# 1-Schematic_PCnA_FinalProject.net
KiCad netlist of a schematic drawn in EasyEDA
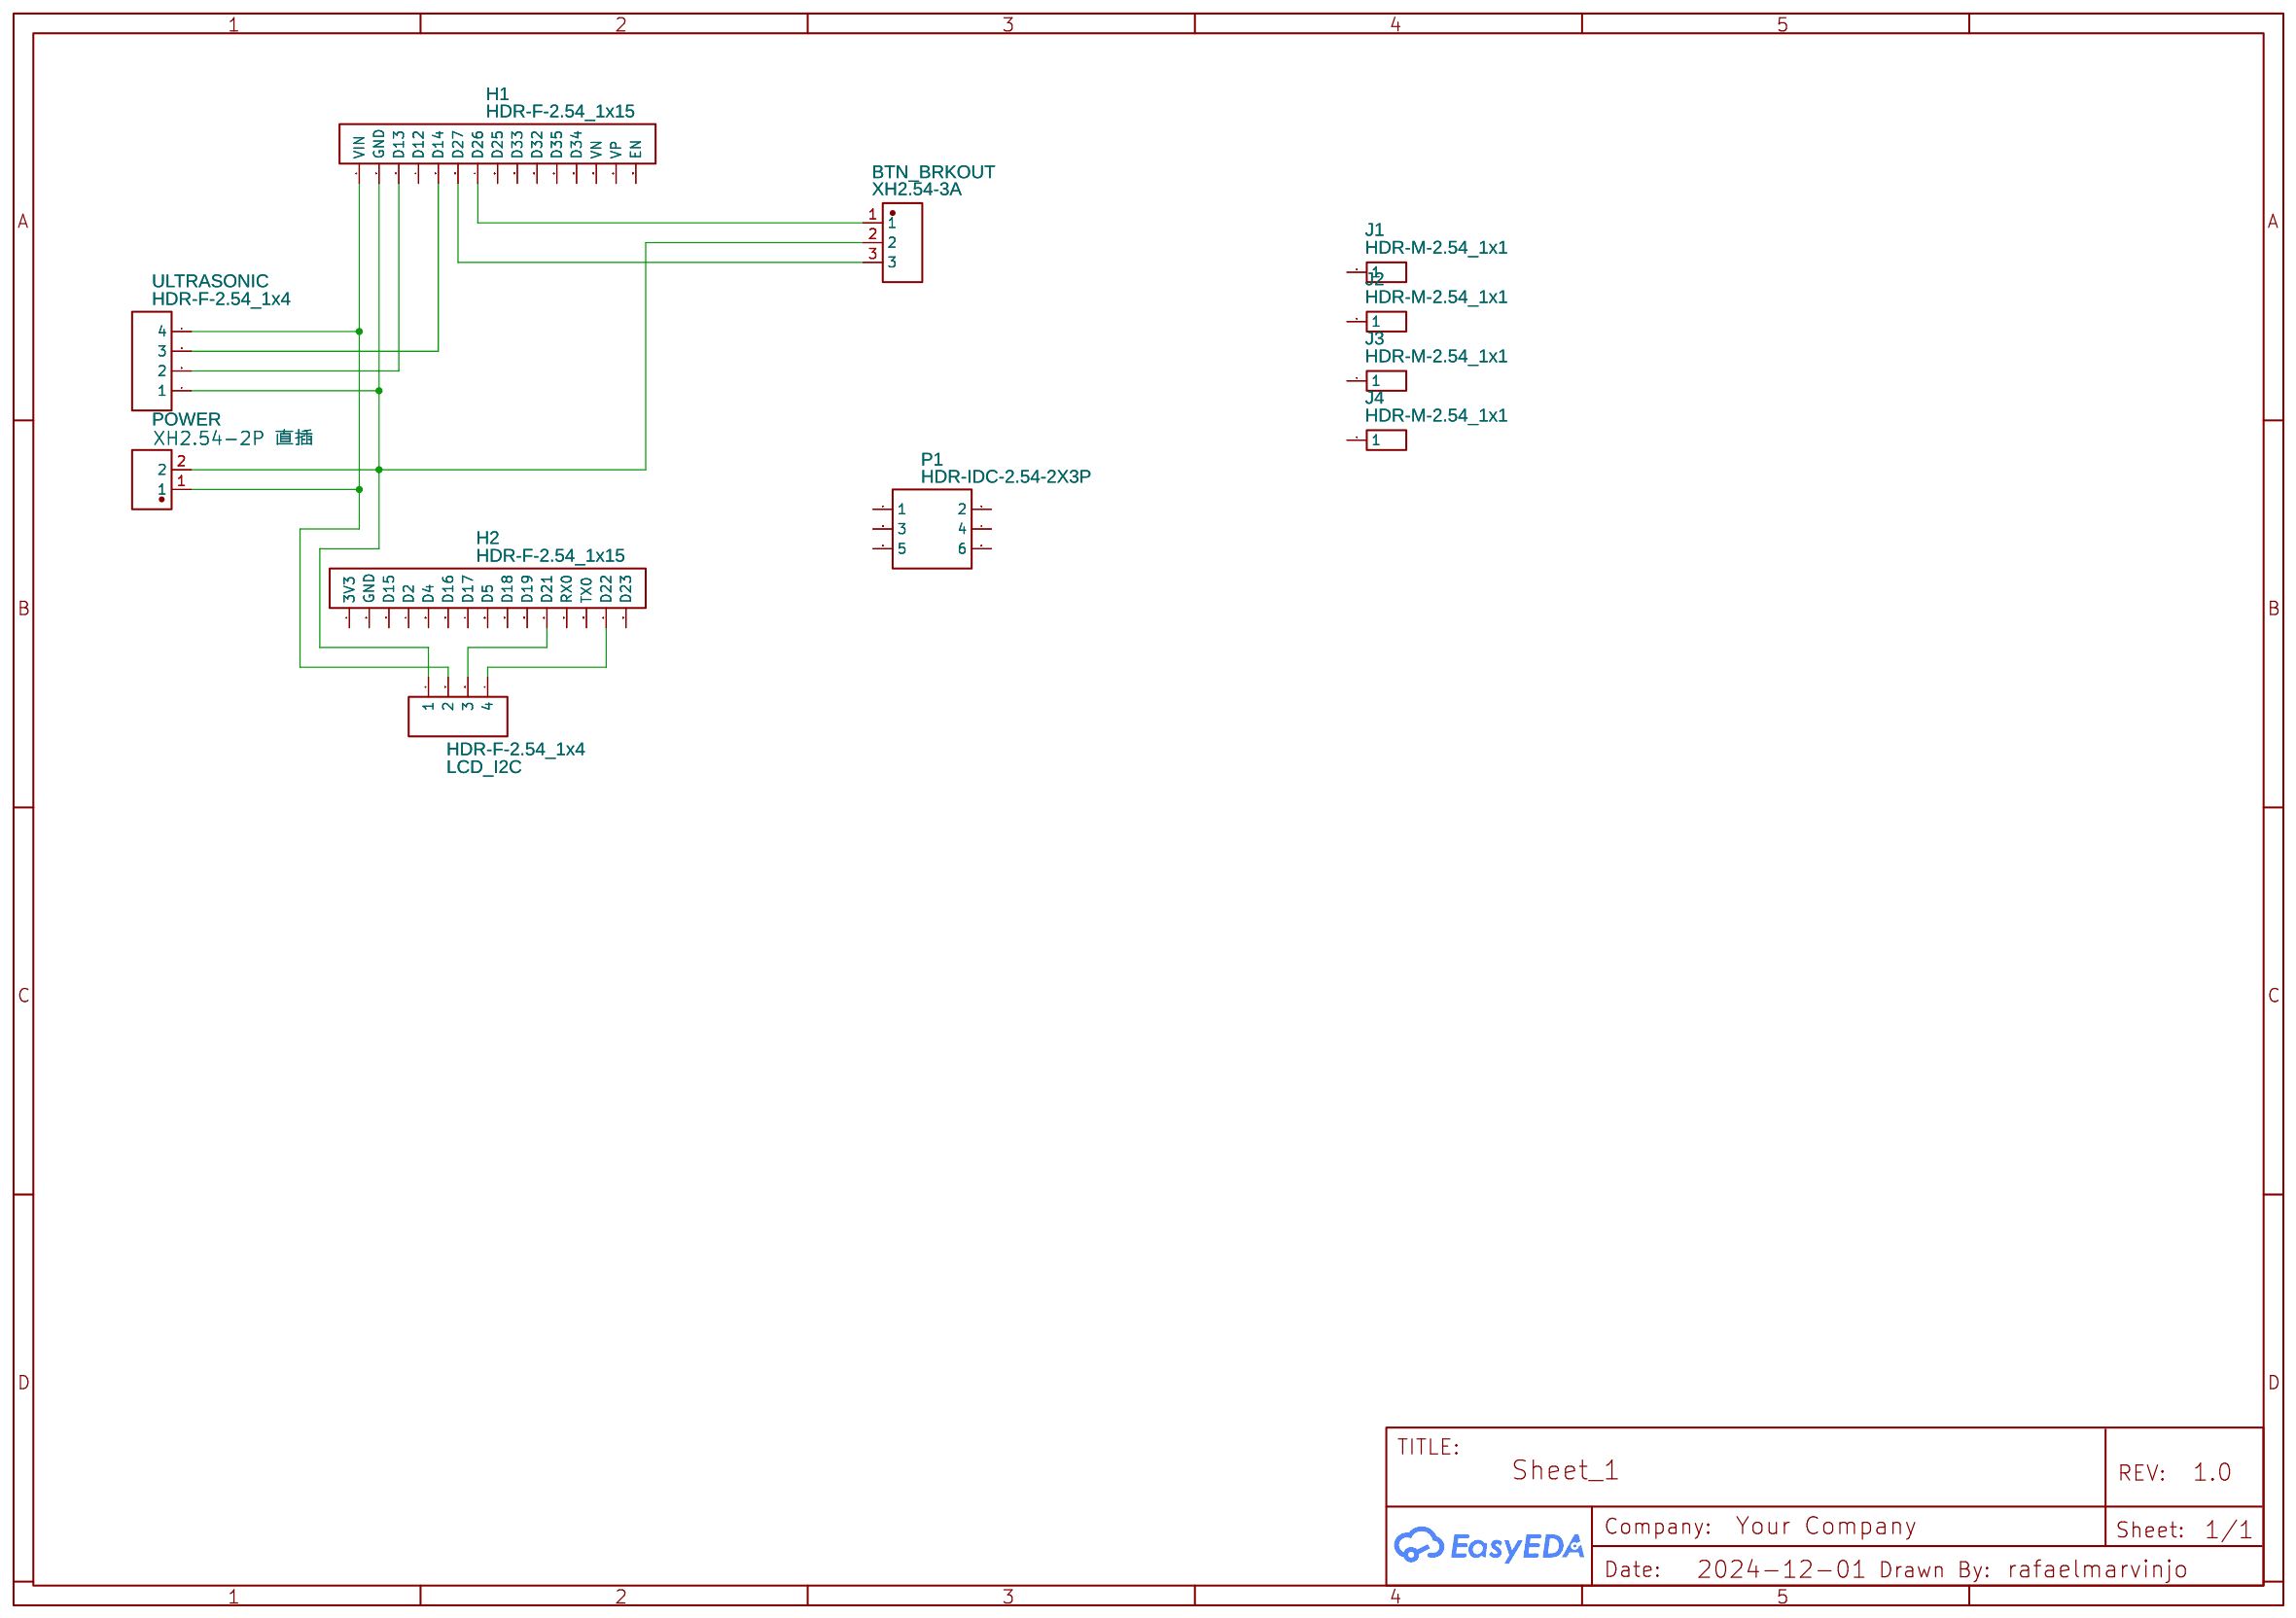
[diagram p0: schematic sheet]

(export (version "E")
  (design (tool "Eeschema 10.0.6"))
  (components
    (comp (ref "BTN_BRKOUT") (value "XH2.54-3A") (libsource (lib "") (part "XH2.54-3A")))
    (comp (ref "H1") (value "HDR-F-2.54_1x15") (libsource (lib "") (part "HDR-F-2.54_1x15")))
    (comp (ref "H2") (value "HDR-F-2.54_1x15") (libsource (lib "") (part "HDR-F-2.54_1x15_1")))
    (comp (ref "J1") (value "HDR-M-2.54_1x1") (libsource (lib "") (part "HDR-M-2.54_1x1")))
    (comp (ref "J2") (value "HDR-M-2.54_1x1") (libsource (lib "") (part "HDR-M-2.54_1x1")))
    (comp (ref "J3") (value "HDR-M-2.54_1x1") (libsource (lib "") (part "HDR-M-2.54_1x1")))
    (comp (ref "J4") (value "HDR-M-2.54_1x1") (libsource (lib "") (part "HDR-M-2.54_1x1")))
    (comp (ref "LCD_I2C") (value "HDR-F-2.54_1x4") (libsource (lib "") (part "HDR-F-2.54_1x4_1")))
    (comp (ref "P1")
      (value "HDR-IDC-2.54-2X3P")
      (fields (field (name "Manufacturer Part") "2X3 2.54mm IDC Box") (field (name "Manufacturer") "BOOMELE"))
      (libsource (lib "") (part "HDR-IDC-2.54-2X3P"))
    )
    (comp (ref "POWER") (value "XH2.54-2P 直插") (libsource (lib "") (part "XH2.54-2P 直插")))
    (comp (ref "ULTRASONIC") (value "HDR-F-2.54_1x4") (libsource (lib "") (part "HDR-F-2.54_1x4")))
  )
  (nets
    (net (code "1") (name "Net-(H1-D13)") (class "Default")
      (node (ref "H1") (pin "3") (pinfunction "D13_3") (pintype "unspecified"))
      (node (ref "ULTRASONIC") (pin "2") (pinfunction "2_2") (pintype "unspecified"))
    )
    (net (code "2") (name "Net-(H1-D14)") (class "Default")
      (node (ref "H1") (pin "5") (pinfunction "D14_5") (pintype "unspecified"))
      (node (ref "ULTRASONIC") (pin "3") (pinfunction "3_3") (pintype "unspecified"))
    )
    (net (code "3") (name "Net-(H1-D26)") (class "Default")
      (node (ref "BTN_BRKOUT") (pin "1") (pinfunction "1_1") (pintype "unspecified"))
      (node (ref "H1") (pin "7") (pinfunction "D26_7") (pintype "unspecified"))
    )
    (net (code "4") (name "Net-(H1-D27)") (class "Default")
      (node (ref "BTN_BRKOUT") (pin "3") (pinfunction "3_3") (pintype "unspecified"))
      (node (ref "H1") (pin "6") (pinfunction "D27_6") (pintype "unspecified"))
    )
    (net (code "5") (name "Net-(H1-GND)") (class "Default")
      (node (ref "BTN_BRKOUT") (pin "2") (pinfunction "2_2") (pintype "unspecified"))
      (node (ref "H1") (pin "2") (pinfunction "GND_2") (pintype "unspecified"))
      (node (ref "LCD_I2C") (pin "1") (pinfunction "1_1") (pintype "unspecified"))
      (node (ref "POWER") (pin "2") (pinfunction "2_2") (pintype "unspecified"))
      (node (ref "ULTRASONIC") (pin "1") (pinfunction "1_1") (pintype "unspecified"))
    )
    (net (code "6") (name "Net-(H1-VIN)") (class "Default")
      (node (ref "H1") (pin "1") (pinfunction "VIN_1") (pintype "unspecified"))
      (node (ref "LCD_I2C") (pin "2") (pinfunction "2_2") (pintype "unspecified"))
      (node (ref "POWER") (pin "1") (pinfunction "1_1") (pintype "unspecified"))
      (node (ref "ULTRASONIC") (pin "4") (pinfunction "4_4") (pintype "unspecified"))
    )
    (net (code "7") (name "Net-(H2-D21)") (class "Default")
      (node (ref "H2") (pin "11") (pinfunction "D21_11") (pintype "unspecified"))
      (node (ref "LCD_I2C") (pin "3") (pinfunction "3_3") (pintype "unspecified"))
    )
    (net (code "8") (name "Net-(H2-D22)") (class "Default")
      (node (ref "H2") (pin "14") (pinfunction "D22_14") (pintype "unspecified"))
      (node (ref "LCD_I2C") (pin "4") (pinfunction "4_4") (pintype "unspecified"))
    )
    (net (code "9") (name "unconnected-(H1-D12-Pad4)") (class "Default")
      (node (ref "H1") (pin "4") (pinfunction "D12_4") (pintype "unspecified"))
    )
    (net (code "10") (name "unconnected-(H1-D25-Pad8)") (class "Default")
      (node (ref "H1") (pin "8") (pinfunction "D25_8") (pintype "unspecified"))
    )
    (net (code "11") (name "unconnected-(H1-D32-Pad10)") (class "Default")
      (node (ref "H1") (pin "10") (pinfunction "D32_10") (pintype "unspecified"))
    )
    (net (code "12") (name "unconnected-(H1-D33-Pad9)") (class "Default")
      (node (ref "H1") (pin "9") (pinfunction "D33_9") (pintype "unspecified"))
    )
    (net (code "13") (name "unconnected-(H1-D34-Pad12)") (class "Default")
      (node (ref "H1") (pin "12") (pinfunction "D34_12") (pintype "unspecified"))
    )
    (net (code "14") (name "unconnected-(H1-D35-Pad11)") (class "Default")
      (node (ref "H1") (pin "11") (pinfunction "D35_11") (pintype "unspecified"))
    )
    (net (code "15") (name "unconnected-(H1-EN-Pad15)") (class "Default")
      (node (ref "H1") (pin "15") (pinfunction "EN_15") (pintype "unspecified"))
    )
    (net (code "16") (name "unconnected-(H1-VN-Pad13)") (class "Default")
      (node (ref "H1") (pin "13") (pinfunction "VN_13") (pintype "unspecified"))
    )
    (net (code "17") (name "unconnected-(H1-VP-Pad14)") (class "Default")
      (node (ref "H1") (pin "14") (pinfunction "VP_14") (pintype "unspecified"))
    )
    (net (code "18") (name "unconnected-(H2-3V3-Pad1)") (class "Default")
      (node (ref "H2") (pin "1") (pinfunction "3V3_1") (pintype "unspecified"))
    )
    (net (code "19") (name "unconnected-(H2-D2-Pad4)") (class "Default")
      (node (ref "H2") (pin "4") (pinfunction "D2_4") (pintype "unspecified"))
    )
    (net (code "20") (name "unconnected-(H2-D4-Pad5)") (class "Default")
      (node (ref "H2") (pin "5") (pinfunction "D4_5") (pintype "unspecified"))
    )
    (net (code "21") (name "unconnected-(H2-D5-Pad8)") (class "Default")
      (node (ref "H2") (pin "8") (pinfunction "D5_8") (pintype "unspecified"))
    )
    (net (code "22") (name "unconnected-(H2-D15-Pad3)") (class "Default")
      (node (ref "H2") (pin "3") (pinfunction "D15_3") (pintype "unspecified"))
    )
    (net (code "23") (name "unconnected-(H2-D16-Pad6)") (class "Default")
      (node (ref "H2") (pin "6") (pinfunction "D16_6") (pintype "unspecified"))
    )
    (net (code "24") (name "unconnected-(H2-D17-Pad7)") (class "Default")
      (node (ref "H2") (pin "7") (pinfunction "D17_7") (pintype "unspecified"))
    )
    (net (code "25") (name "unconnected-(H2-D18-Pad9)") (class "Default")
      (node (ref "H2") (pin "9") (pinfunction "D18_9") (pintype "unspecified"))
    )
    (net (code "26") (name "unconnected-(H2-D19-Pad10)") (class "Default")
      (node (ref "H2") (pin "10") (pinfunction "D19_10") (pintype "unspecified"))
    )
    (net (code "27") (name "unconnected-(H2-D23-Pad15)") (class "Default")
      (node (ref "H2") (pin "15") (pinfunction "D23_15") (pintype "unspecified"))
    )
    (net (code "28") (name "unconnected-(H2-GND-Pad2)") (class "Default")
      (node (ref "H2") (pin "2") (pinfunction "GND_2") (pintype "unspecified"))
    )
    (net (code "29") (name "unconnected-(H2-RX0-Pad12)") (class "Default")
      (node (ref "H2") (pin "12") (pinfunction "RX0_12") (pintype "unspecified"))
    )
    (net (code "30") (name "unconnected-(H2-TX0-Pad13)") (class "Default")
      (node (ref "H2") (pin "13") (pinfunction "TX0_13") (pintype "unspecified"))
    )
    (net (code "31") (name "unconnected-(J1-Pad1)") (class "Default")
      (node (ref "J1") (pin "1") (pinfunction "1_1") (pintype "input"))
    )
    (net (code "32") (name "unconnected-(J2-Pad1)") (class "Default")
      (node (ref "J2") (pin "1") (pinfunction "1_1") (pintype "input"))
    )
    (net (code "33") (name "unconnected-(J3-Pad1)") (class "Default")
      (node (ref "J3") (pin "1") (pinfunction "1_1") (pintype "input"))
    )
    (net (code "34") (name "unconnected-(J4-Pad1)") (class "Default")
      (node (ref "J4") (pin "1") (pinfunction "1_1") (pintype "input"))
    )
    (net (code "35") (name "unconnected-(P1-Pad1)") (class "Default")
      (node (ref "P1") (pin "1") (pinfunction "1_1") (pintype "unspecified"))
    )
    (net (code "36") (name "unconnected-(P1-Pad2)") (class "Default")
      (node (ref "P1") (pin "2") (pinfunction "2_2") (pintype "unspecified"))
    )
    (net (code "37") (name "unconnected-(P1-Pad3)") (class "Default")
      (node (ref "P1") (pin "3") (pinfunction "3_3") (pintype "unspecified"))
    )
    (net (code "38") (name "unconnected-(P1-Pad4)") (class "Default")
      (node (ref "P1") (pin "4") (pinfunction "4_4") (pintype "unspecified"))
    )
    (net (code "39") (name "unconnected-(P1-Pad5)") (class "Default")
      (node (ref "P1") (pin "5") (pinfunction "5_5") (pintype "unspecified"))
    )
    (net (code "40") (name "unconnected-(P1-Pad6)") (class "Default")
      (node (ref "P1") (pin "6") (pinfunction "6_6") (pintype "unspecified"))
    )
  )
)
